# 9_RGB_TOUCH.net
KiCad netlist of a schematic drawn in Altium Designer
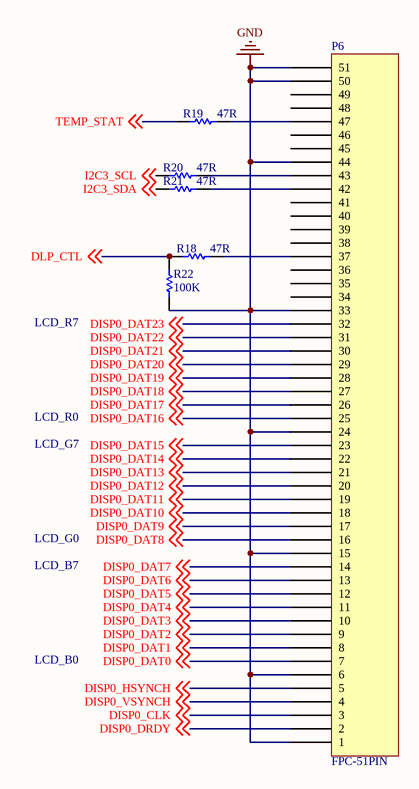
[diagram p0: 9.RGB&TOUCH.SchDoc]

(export (version "E")
  (design (tool "Eeschema 10.0.6"))
  (components
    (comp (ref "P6")
      (value "FPC-51PIN")
      (footprint "FH26-51S-0.3SHW")
      (libsource (lib "TANK") (part "FPC-51PIN"))
    )
    (comp (ref "R18")
      (value "47R")
      (footprint "0603")
      (description "Resistor")
      (libsource (lib "*") (part "Res1"))
    )
    (comp (ref "R19")
      (value "47R")
      (footprint "0603")
      (description "Resistor")
      (libsource (lib "*") (part "Res1"))
    )
    (comp (ref "R20")
      (value "47R")
      (footprint "0603")
      (description "Resistor")
      (libsource (lib "*") (part "Res1"))
    )
    (comp (ref "R21")
      (value "47R")
      (footprint "0603")
      (description "Resistor")
      (libsource (lib "*") (part "Res1"))
    )
    (comp (ref "R22")
      (value "100K")
      (footprint "0603")
      (description "Resistor")
      (libsource (lib "*") (part "Res1"))
    )
  )
  (nets
    (net (code "1") (name "DISP0_CLK") (class "Default")
      (node (ref "P6") (pin "3") (pinfunction "3_3") (pintype "passive"))
    )
    (net (code "2") (name "DISP0_DAT0") (class "Default")
      (node (ref "P6") (pin "7") (pinfunction "7_7") (pintype "passive"))
    )
    (net (code "3") (name "DISP0_DAT1") (class "Default")
      (node (ref "P6") (pin "8") (pinfunction "8_8") (pintype "passive"))
    )
    (net (code "4") (name "DISP0_DAT2") (class "Default")
      (node (ref "P6") (pin "9") (pinfunction "9_9") (pintype "passive"))
    )
    (net (code "5") (name "DISP0_DAT3") (class "Default")
      (node (ref "P6") (pin "10") (pinfunction "10_10") (pintype "passive"))
    )
    (net (code "6") (name "DISP0_DAT4") (class "Default")
      (node (ref "P6") (pin "11") (pinfunction "11_11") (pintype "passive"))
    )
    (net (code "7") (name "DISP0_DAT5") (class "Default")
      (node (ref "P6") (pin "12") (pinfunction "12_12") (pintype "passive"))
    )
    (net (code "8") (name "DISP0_DAT6") (class "Default")
      (node (ref "P6") (pin "13") (pinfunction "13_13") (pintype "passive"))
    )
    (net (code "9") (name "DISP0_DAT7") (class "Default")
      (node (ref "P6") (pin "14") (pinfunction "14_14") (pintype "passive"))
    )
    (net (code "10") (name "DISP0_DAT8") (class "Default")
      (node (ref "P6") (pin "16") (pinfunction "16_16") (pintype "passive"))
    )
    (net (code "11") (name "DISP0_DAT9") (class "Default")
      (node (ref "P6") (pin "17") (pinfunction "17_17") (pintype "passive"))
    )
    (net (code "12") (name "DISP0_DAT10") (class "Default")
      (node (ref "P6") (pin "18") (pinfunction "18_18") (pintype "passive"))
    )
    (net (code "13") (name "DISP0_DAT11") (class "Default")
      (node (ref "P6") (pin "19") (pinfunction "19_19") (pintype "passive"))
    )
    (net (code "14") (name "DISP0_DAT12") (class "Default")
      (node (ref "P6") (pin "20") (pinfunction "20_20") (pintype "passive"))
    )
    (net (code "15") (name "DISP0_DAT13") (class "Default")
      (node (ref "P6") (pin "21") (pinfunction "21_21") (pintype "passive"))
    )
    (net (code "16") (name "DISP0_DAT14") (class "Default")
      (node (ref "P6") (pin "22") (pinfunction "22_22") (pintype "passive"))
    )
    (net (code "17") (name "DISP0_DAT15") (class "Default")
      (node (ref "P6") (pin "23") (pinfunction "23_23") (pintype "passive"))
    )
    (net (code "18") (name "DISP0_DAT16") (class "Default")
      (node (ref "P6") (pin "25") (pinfunction "25_25") (pintype "passive"))
    )
    (net (code "19") (name "DISP0_DAT17") (class "Default")
      (node (ref "P6") (pin "26") (pinfunction "26_26") (pintype "passive"))
    )
    (net (code "20") (name "DISP0_DAT18") (class "Default")
      (node (ref "P6") (pin "27") (pinfunction "27_27") (pintype "passive"))
    )
    (net (code "21") (name "DISP0_DAT19") (class "Default")
      (node (ref "P6") (pin "28") (pinfunction "28_28") (pintype "passive"))
    )
    (net (code "22") (name "DISP0_DAT20") (class "Default")
      (node (ref "P6") (pin "29") (pinfunction "29_29") (pintype "passive"))
    )
    (net (code "23") (name "DISP0_DAT21") (class "Default")
      (node (ref "P6") (pin "30") (pinfunction "30_30") (pintype "passive"))
    )
    (net (code "24") (name "DISP0_DAT22") (class "Default")
      (node (ref "P6") (pin "31") (pinfunction "31_31") (pintype "passive"))
    )
    (net (code "25") (name "DISP0_DAT23") (class "Default")
      (node (ref "P6") (pin "32") (pinfunction "32_32") (pintype "passive"))
    )
    (net (code "26") (name "DISP0_DRDY") (class "Default")
      (node (ref "P6") (pin "2") (pinfunction "2_2") (pintype "passive"))
    )
    (net (code "27") (name "DISP0_HSYNCH") (class "Default")
      (node (ref "P6") (pin "5") (pinfunction "5_5") (pintype "passive"))
    )
    (net (code "28") (name "DISP0_VSYNCH") (class "Default")
      (node (ref "P6") (pin "4") (pinfunction "4_4") (pintype "passive"))
    )
    (net (code "29") (name "DLP_CTL") (class "Default")
      (node (ref "R18") (pin "1") (pinfunction "1_1") (pintype "passive"))
      (node (ref "R22") (pin "2") (pinfunction "2_2") (pintype "passive"))
    )
    (net (code "30") (name "GND") (class "Default")
      (node (ref "P6") (pin "1") (pinfunction "1_1") (pintype "passive"))
      (node (ref "P6") (pin "15") (pinfunction "15_15") (pintype "passive"))
      (node (ref "P6") (pin "24") (pinfunction "24_24") (pintype "passive"))
      (node (ref "P6") (pin "33") (pinfunction "33_33") (pintype "passive"))
      (node (ref "P6") (pin "44") (pinfunction "44_44") (pintype "passive"))
      (node (ref "P6") (pin "50") (pinfunction "50_50") (pintype "passive"))
      (node (ref "P6") (pin "51") (pinfunction "51_51") (pintype "passive"))
      (node (ref "P6") (pin "6") (pinfunction "6_6") (pintype "passive"))
      (node (ref "R22") (pin "1") (pinfunction "1_1") (pintype "passive"))
    )
    (net (code "31") (name "I2C3_SCL") (class "Default")
      (node (ref "R20") (pin "1") (pinfunction "1_1") (pintype "passive"))
    )
    (net (code "32") (name "I2C3_SDA") (class "Default")
      (node (ref "R21") (pin "1") (pinfunction "1_1") (pintype "passive"))
    )
    (net (code "33") (name "Net-(P6-Pad37)") (class "Default")
      (node (ref "P6") (pin "37") (pinfunction "37_37") (pintype "passive"))
      (node (ref "R18") (pin "2") (pinfunction "2_2") (pintype "passive"))
    )
    (net (code "34") (name "Net-(P6-Pad42)") (class "Default")
      (node (ref "P6") (pin "42") (pinfunction "42_42") (pintype "passive"))
      (node (ref "R21") (pin "2") (pinfunction "2_2") (pintype "passive"))
    )
    (net (code "35") (name "Net-(P6-Pad43)") (class "Default")
      (node (ref "P6") (pin "43") (pinfunction "43_43") (pintype "passive"))
      (node (ref "R20") (pin "2") (pinfunction "2_2") (pintype "passive"))
    )
    (net (code "36") (name "Net-(P6-Pad47)") (class "Default")
      (node (ref "P6") (pin "47") (pinfunction "47_47") (pintype "passive"))
      (node (ref "R19") (pin "2") (pinfunction "2_2") (pintype "passive"))
    )
    (net (code "37") (name "TEMP_STAT") (class "Default")
      (node (ref "R19") (pin "1") (pinfunction "1_1") (pintype "passive"))
    )
    (net (code "38") (name "unconnected-(P6-Pad34)") (class "Default")
      (node (ref "P6") (pin "34") (pinfunction "34_34") (pintype "passive"))
    )
    (net (code "39") (name "unconnected-(P6-Pad35)") (class "Default")
      (node (ref "P6") (pin "35") (pinfunction "35_35") (pintype "passive"))
    )
    (net (code "40") (name "unconnected-(P6-Pad36)") (class "Default")
      (node (ref "P6") (pin "36") (pinfunction "36_36") (pintype "passive"))
    )
    (net (code "41") (name "unconnected-(P6-Pad38)") (class "Default")
      (node (ref "P6") (pin "38") (pinfunction "38_38") (pintype "passive"))
    )
    (net (code "42") (name "unconnected-(P6-Pad39)") (class "Default")
      (node (ref "P6") (pin "39") (pinfunction "39_39") (pintype "passive"))
    )
    (net (code "43") (name "unconnected-(P6-Pad40)") (class "Default")
      (node (ref "P6") (pin "40") (pinfunction "40_40") (pintype "passive"))
    )
    (net (code "44") (name "unconnected-(P6-Pad41)") (class "Default")
      (node (ref "P6") (pin "41") (pinfunction "41_41") (pintype "passive"))
    )
    (net (code "45") (name "unconnected-(P6-Pad45)") (class "Default")
      (node (ref "P6") (pin "45") (pinfunction "45_45") (pintype "passive"))
    )
    (net (code "46") (name "unconnected-(P6-Pad46)") (class "Default")
      (node (ref "P6") (pin "46") (pinfunction "46_46") (pintype "passive"))
    )
    (net (code "47") (name "unconnected-(P6-Pad48)") (class "Default")
      (node (ref "P6") (pin "48") (pinfunction "48_48") (pintype "passive"))
    )
    (net (code "48") (name "unconnected-(P6-Pad49)") (class "Default")
      (node (ref "P6") (pin "49") (pinfunction "49_49") (pintype "passive"))
    )
  )
)
